# Lights.net
KiCad netlist of a schematic drawn in Altium Designer
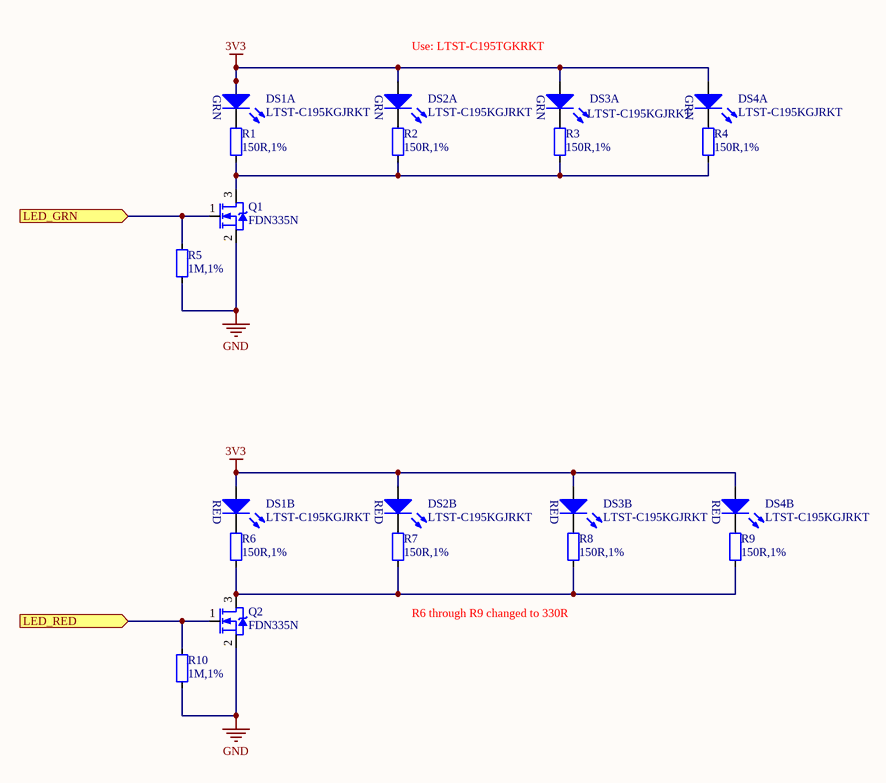
[diagram p0: Lights.SchDoc]

(export (version "E")
  (design (tool "Eeschema 10.0.6"))
  (components
    (comp (ref "DS1")
      (value "LTST-C195KGJRKT")
      (footprint "LITEON_LTST-C195KGJRKT")
      (description "LED GREEN/RED BICOLOR 0606 SMD")
      (fields (field (name "MANUFACTURER") "Lite-On Inc"))
      (libsource (lib "library") (part "LITEON_LTST-C195KGJRKT"))
    )
    (comp (ref "DS2")
      (value "LTST-C195KGJRKT")
      (footprint "LITEON_LTST-C195KGJRKT")
      (description "LED GREEN/RED BICOLOR 0606 SMD")
      (fields (field (name "MANUFACTURER") "Lite-On Inc"))
      (libsource (lib "library") (part "LITEON_LTST-C195KGJRKT"))
    )
    (comp (ref "DS3")
      (value "LTST-C195KGJRKT")
      (footprint "LITEON_LTST-C195KGJRKT")
      (description "LED GREEN/RED BICOLOR 0606 SMD")
      (fields (field (name "MANUFACTURER") "Lite-On Inc"))
      (libsource (lib "library") (part "LITEON_LTST-C195KGJRKT"))
    )
    (comp (ref "DS4")
      (value "LTST-C195KGJRKT")
      (footprint "LITEON_LTST-C195KGJRKT")
      (description "LED GREEN/RED BICOLOR 0606 SMD")
      (fields (field (name "MANUFACTURER") "Lite-On Inc"))
      (libsource (lib "library") (part "LITEON_LTST-C195KGJRKT"))
    )
    (comp (ref "Q1")
      (value "FDN335N")
      (footprint "SOT95P230X110-3N_SOT23")
      (description "MOSFET N-CH 20V 1.7A SSOT3")
      (fields (field (name "MANUFACTURER") "Fairchild Semiconductor"))
      (libsource (lib "library") (part "MOSFET-N_1"))
    )
    (comp (ref "Q2")
      (value "FDN335N")
      (footprint "SOT95P230X110-3N_SOT23")
      (description "MOSFET N-CH 20V 1.7A SSOT3")
      (fields (field (name "MANUFACTURER") "Fairchild Semiconductor"))
      (libsource (lib "library") (part "MOSFET-N_1"))
    )
    (comp (ref "R1")
      (value "150R,1%")
      (footprint "RESC1608X06N_0603")
      (description "RES 150 OHM 1/10W 1% 0603 SMD")
      (fields (field (name "MANUFACTURER") "Yageo") (field (name "POWER") "0.1W"))
      (libsource (lib "library") (part "RESISTOR_1"))
    )
    (comp (ref "R2")
      (value "150R,1%")
      (footprint "RESC1608X06N_0603")
      (description "RES 150 OHM 1/10W 1% 0603 SMD")
      (fields (field (name "MANUFACTURER") "Yageo") (field (name "POWER") "0.1W"))
      (libsource (lib "library") (part "RESISTOR_1"))
    )
    (comp (ref "R3")
      (value "150R,1%")
      (footprint "RESC1608X06N_0603")
      (description "RES 150 OHM 1/10W 1% 0603 SMD")
      (fields (field (name "MANUFACTURER") "Yageo") (field (name "POWER") "0.1W"))
      (libsource (lib "library") (part "RESISTOR_1"))
    )
    (comp (ref "R4")
      (value "150R,1%")
      (footprint "RESC1608X06N_0603")
      (description "RES 150 OHM 1/10W 1% 0603 SMD")
      (fields (field (name "MANUFACTURER") "Yageo") (field (name "POWER") "0.1W"))
      (libsource (lib "library") (part "RESISTOR_1"))
    )
    (comp (ref "R5")
      (value "1M,1%")
      (footprint "RESC1608X06N_0603")
      (description "RES 1.00M OHM 1/10W 1% 0603 SMD")
      (fields (field (name "MANUFACTURER") "Yageo") (field (name "POWER") "0.1W"))
      (libsource (lib "") (part "RESISTOR_1_1"))
    )
    (comp (ref "R6")
      (value "150R,1%")
      (footprint "RESC1608X06N_0603")
      (description "RES 150 OHM 1/10W 1% 0603 SMD")
      (fields (field (name "MANUFACTURER") "Yageo") (field (name "POWER") "0.1W"))
      (libsource (lib "library") (part "RESISTOR_1"))
    )
    (comp (ref "R7")
      (value "150R,1%")
      (footprint "RESC1608X06N_0603")
      (description "RES 150 OHM 1/10W 1% 0603 SMD")
      (fields (field (name "MANUFACTURER") "Yageo") (field (name "POWER") "0.1W"))
      (libsource (lib "library") (part "RESISTOR_1"))
    )
    (comp (ref "R8")
      (value "150R,1%")
      (footprint "RESC1608X06N_0603")
      (description "RES 150 OHM 1/10W 1% 0603 SMD")
      (fields (field (name "MANUFACTURER") "Yageo") (field (name "POWER") "0.1W"))
      (libsource (lib "library") (part "RESISTOR_1"))
    )
    (comp (ref "R9")
      (value "150R,1%")
      (footprint "RESC1608X06N_0603")
      (description "RES 150 OHM 1/10W 1% 0603 SMD")
      (fields (field (name "MANUFACTURER") "Yageo") (field (name "POWER") "0.1W"))
      (libsource (lib "library") (part "RESISTOR_1"))
    )
    (comp (ref "R10")
      (value "1M,1%")
      (footprint "RESC1608X06N_0603")
      (description "RES 1.00M OHM 1/10W 1% 0603 SMD")
      (fields (field (name "MANUFACTURER") "Yageo") (field (name "POWER") "0.1W"))
      (libsource (lib "") (part "RESISTOR_1_1"))
    )
  )
  (nets
    (net (code "1") (name "/LED_GRN") (class "Default")
      (node (ref "Q1") (pin "1") (pinfunction "G_1") (pintype "passive"))
      (node (ref "R5") (pin "1") (pinfunction "1_1") (pintype "passive"))
    )
    (net (code "2") (name "/LED_RED") (class "Default")
      (node (ref "Q2") (pin "1") (pinfunction "G_1") (pintype "passive"))
      (node (ref "R10") (pin "1") (pinfunction "1_1") (pintype "passive"))
    )
    (net (code "3") (name "3V3") (class "Default")
      (node (ref "DS1") (pin "1") (pinfunction "AG_1") (pintype "passive"))
      (node (ref "DS1") (pin "2") (pinfunction "AR_2") (pintype "passive"))
      (node (ref "DS2") (pin "1") (pinfunction "AG_1") (pintype "passive"))
      (node (ref "DS2") (pin "2") (pinfunction "AR_2") (pintype "passive"))
      (node (ref "DS3") (pin "1") (pinfunction "AG_1") (pintype "passive"))
      (node (ref "DS3") (pin "2") (pinfunction "AR_2") (pintype "passive"))
      (node (ref "DS4") (pin "1") (pinfunction "AG_1") (pintype "passive"))
      (node (ref "DS4") (pin "2") (pinfunction "AR_2") (pintype "passive"))
    )
    (net (code "4") (name "GND") (class "Default")
      (node (ref "Q1") (pin "2") (pinfunction "S_2") (pintype "passive"))
      (node (ref "Q2") (pin "2") (pinfunction "S_2") (pintype "passive"))
      (node (ref "R10") (pin "2") (pinfunction "2_2") (pintype "passive"))
      (node (ref "R5") (pin "2") (pinfunction "2_2") (pintype "passive"))
    )
    (net (code "5") (name "Net-(DS1A-CG)") (class "Default")
      (node (ref "DS1") (pin "3") (pinfunction "CG_3") (pintype "passive"))
      (node (ref "R1") (pin "2") (pinfunction "2_2") (pintype "passive"))
    )
    (net (code "6") (name "Net-(DS1B-CR)") (class "Default")
      (node (ref "DS1") (pin "4") (pinfunction "CR_4") (pintype "passive"))
      (node (ref "R6") (pin "2") (pinfunction "2_2") (pintype "passive"))
    )
    (net (code "7") (name "Net-(DS2A-CG)") (class "Default")
      (node (ref "DS2") (pin "3") (pinfunction "CG_3") (pintype "passive"))
      (node (ref "R2") (pin "2") (pinfunction "2_2") (pintype "passive"))
    )
    (net (code "8") (name "Net-(DS2B-CR)") (class "Default")
      (node (ref "DS2") (pin "4") (pinfunction "CR_4") (pintype "passive"))
      (node (ref "R7") (pin "2") (pinfunction "2_2") (pintype "passive"))
    )
    (net (code "9") (name "Net-(DS3A-CG)") (class "Default")
      (node (ref "DS3") (pin "3") (pinfunction "CG_3") (pintype "passive"))
      (node (ref "R3") (pin "2") (pinfunction "2_2") (pintype "passive"))
    )
    (net (code "10") (name "Net-(DS3B-CR)") (class "Default")
      (node (ref "DS3") (pin "4") (pinfunction "CR_4") (pintype "passive"))
      (node (ref "R8") (pin "2") (pinfunction "2_2") (pintype "passive"))
    )
    (net (code "11") (name "Net-(DS4A-CG)") (class "Default")
      (node (ref "DS4") (pin "3") (pinfunction "CG_3") (pintype "passive"))
      (node (ref "R4") (pin "2") (pinfunction "2_2") (pintype "passive"))
    )
    (net (code "12") (name "Net-(DS4B-CR)") (class "Default")
      (node (ref "DS4") (pin "4") (pinfunction "CR_4") (pintype "passive"))
      (node (ref "R9") (pin "2") (pinfunction "2_2") (pintype "passive"))
    )
    (net (code "13") (name "Net-(Q1-D)") (class "Default")
      (node (ref "Q1") (pin "3") (pinfunction "D_3") (pintype "passive"))
      (node (ref "R1") (pin "1") (pinfunction "1_1") (pintype "passive"))
      (node (ref "R2") (pin "1") (pinfunction "1_1") (pintype "passive"))
      (node (ref "R3") (pin "1") (pinfunction "1_1") (pintype "passive"))
      (node (ref "R4") (pin "1") (pinfunction "1_1") (pintype "passive"))
    )
    (net (code "14") (name "Net-(Q2-D)") (class "Default")
      (node (ref "Q2") (pin "3") (pinfunction "D_3") (pintype "passive"))
      (node (ref "R6") (pin "1") (pinfunction "1_1") (pintype "passive"))
      (node (ref "R7") (pin "1") (pinfunction "1_1") (pintype "passive"))
      (node (ref "R8") (pin "1") (pinfunction "1_1") (pintype "passive"))
      (node (ref "R9") (pin "1") (pinfunction "1_1") (pintype "passive"))
    )
  )
)
